# sequencer.net
KiCad netlist of a schematic drawn in EAGLE
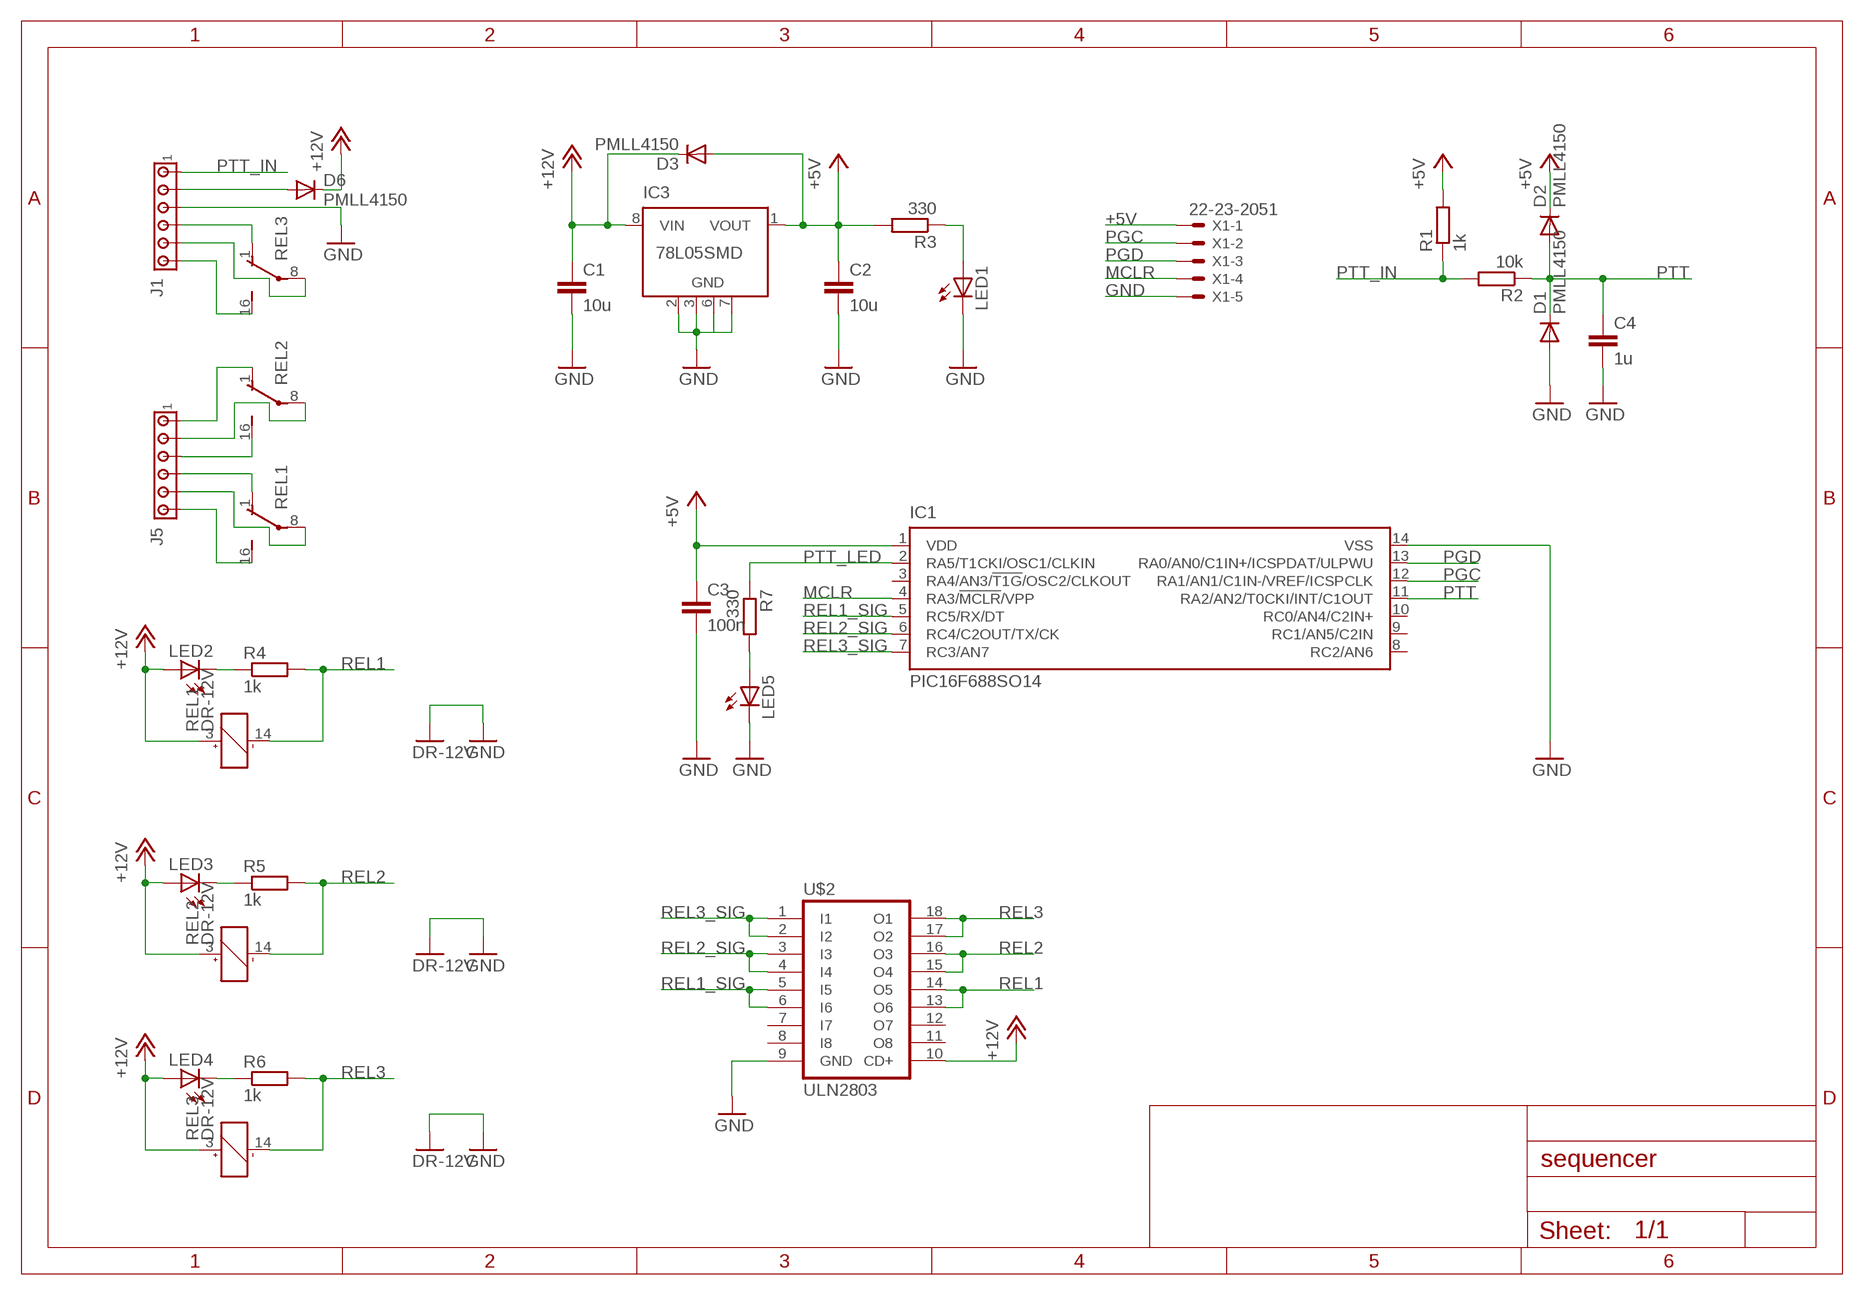
[diagram p0: schematic, sheet 1]

(export (version "E")
  (design (tool "Eeschema 10.0.6"))
  (components
    (comp (ref "C1")
      (value "10u")
      (footprint "eagle-import:C1206")
      (libsource (lib "eagle-import") (part "CAPACITORC1206"))
    )
    (comp (ref "C2")
      (value "10u")
      (footprint "eagle-import:C1206")
      (libsource (lib "eagle-import") (part "CAPACITORC1206"))
    )
    (comp (ref "C3")
      (value "100n")
      (footprint "eagle-import:C1206")
      (libsource (lib "eagle-import") (part "CAPACITORC1206"))
    )
    (comp (ref "C4")
      (value "1u")
      (footprint "eagle-import:C1206")
      (libsource (lib "eagle-import") (part "CAPACITORC1206"))
    )
    (comp (ref "D1")
      (value "PMLL4150")
      (footprint "eagle-import:SOD80C")
      (libsource (lib "eagle-import") (part "PMLL4150"))
    )
    (comp (ref "D2")
      (value "PMLL4150")
      (footprint "eagle-import:SOD80C")
      (libsource (lib "eagle-import") (part "PMLL4150"))
    )
    (comp (ref "D3")
      (value "PMLL4150")
      (footprint "eagle-import:SOD80C")
      (libsource (lib "eagle-import") (part "PMLL4150"))
    )
    (comp (ref "D6")
      (value "PMLL4150")
      (footprint "eagle-import:SOD80C")
      (libsource (lib "eagle-import") (part "PMLL4150"))
    )
    (comp (ref "IC1")
      (value "PIC16F688SO14")
      (footprint "eagle-import:SO14")
      (libsource (lib "eagle-import") (part "PIC16F688SO14"))
    )
    (comp (ref "IC3")
      (value "78L05SMD")
      (footprint "eagle-import:SO08")
      (libsource (lib "eagle-import") (part "78LSMD05"))
    )
    (comp (ref "J1")
      (value "SL508_6_90SL508_6_90")
      (footprint "eagle-import:SL508_6_90")
      (libsource (lib "eagle-import") (part "SL508_6_90SL508_6_90"))
    )
    (comp (ref "J5")
      (value "SL508_6_90SL508_6_90")
      (footprint "eagle-import:SL508_6_90")
      (libsource (lib "eagle-import") (part "SL508_6_90SL508_6_90"))
    )
    (comp (ref "LED1")
      (value "LEDSMT1206")
      (footprint "eagle-import:1206")
      (libsource (lib "eagle-import") (part "LEDSMT1206"))
    )
    (comp (ref "LED2")
      (value "LEDSMT1206")
      (footprint "eagle-import:1206")
      (libsource (lib "eagle-import") (part "LEDSMT1206"))
    )
    (comp (ref "LED3")
      (value "LEDSMT1206")
      (footprint "eagle-import:1206")
      (libsource (lib "eagle-import") (part "LEDSMT1206"))
    )
    (comp (ref "LED4")
      (value "LEDSMT1206")
      (footprint "eagle-import:1206")
      (libsource (lib "eagle-import") (part "LEDSMT1206"))
    )
    (comp (ref "LED5")
      (value "LEDSMT1206")
      (footprint "eagle-import:1206")
      (libsource (lib "eagle-import") (part "LEDSMT1206"))
    )
    (comp (ref "R1")
      (value "1k")
      (footprint "eagle-import:R1206")
      (libsource (lib "eagle-import") (part "RESISTORR1206"))
    )
    (comp (ref "R2")
      (value "10k")
      (footprint "eagle-import:R1206")
      (libsource (lib "eagle-import") (part "RESISTORR1206"))
    )
    (comp (ref "R3")
      (value "330")
      (footprint "eagle-import:R1206")
      (libsource (lib "eagle-import") (part "RESISTORR1206"))
    )
    (comp (ref "R4")
      (value "1k")
      (footprint "eagle-import:R1206")
      (libsource (lib "eagle-import") (part "RESISTORR1206"))
    )
    (comp (ref "R5")
      (value "1k")
      (footprint "eagle-import:R1206")
      (libsource (lib "eagle-import") (part "RESISTORR1206"))
    )
    (comp (ref "R6")
      (value "1k")
      (footprint "eagle-import:R1206")
      (libsource (lib "eagle-import") (part "RESISTORR1206"))
    )
    (comp (ref "R7")
      (value "330")
      (footprint "eagle-import:R1206")
      (libsource (lib "eagle-import") (part "RESISTORR1206"))
    )
    (comp (ref "REL1")
      (value "DR-12V")
      (footprint "eagle-import:DR-12V")
      (libsource (lib "eagle-import") (part "DR-12V"))
    )
    (comp (ref "REL2")
      (value "DR-12V")
      (footprint "eagle-import:DR-12V")
      (libsource (lib "eagle-import") (part "DR-12V"))
    )
    (comp (ref "REL3")
      (value "DR-12V")
      (footprint "eagle-import:DR-12V")
      (libsource (lib "eagle-import") (part "DR-12V"))
    )
    (comp (ref "U$2")
      (value "ULN2803")
      (footprint "eagle-import:SO18W")
      (libsource (lib "eagle-import") (part "ULN2803"))
    )
    (comp (ref "X1")
      (value "22-23-2051")
      (footprint "eagle-import:22-23-2051")
      (fields (field (name "MF") "MOLEX"))
      (libsource (lib "eagle-import") (part "22-23-2051"))
    )
  )
  (nets
    (net (code "1") (name "+5V") (class "Default")
      (node (ref "C2") (pin "1") (pinfunction "1_1") (pintype "passive"))
      (node (ref "C3") (pin "1") (pinfunction "1_1") (pintype "passive"))
      (node (ref "D2") (pin "C") (pinfunction "C_C") (pintype "passive"))
      (node (ref "D3") (pin "A") (pinfunction "A_A") (pintype "passive"))
      (node (ref "IC1") (pin "1") (pinfunction "VDD_1") (pintype "power_in"))
      (node (ref "IC3") (pin "1") (pinfunction "VOUT_1") (pintype "output"))
      (node (ref "R1") (pin "2") (pinfunction "2_2") (pintype "passive"))
      (node (ref "R3") (pin "2") (pinfunction "2_2") (pintype "passive"))
      (node (ref "X1") (pin "1") (pinfunction "S_1") (pintype "passive"))
    )
    (net (code "2") (name "+12V") (class "Default")
      (node (ref "C1") (pin "1") (pinfunction "1_1") (pintype "passive"))
      (node (ref "D3") (pin "C") (pinfunction "C_C") (pintype "passive"))
      (node (ref "D6") (pin "C") (pinfunction "C_C") (pintype "passive"))
      (node (ref "IC3") (pin "8") (pinfunction "VIN_8") (pintype "passive"))
      (node (ref "LED2") (pin "A") (pinfunction "A_A") (pintype "passive"))
      (node (ref "LED3") (pin "A") (pinfunction "A_A") (pintype "passive"))
      (node (ref "LED4") (pin "A") (pinfunction "A_A") (pintype "passive"))
      (node (ref "REL1") (pin "3") (pinfunction "+_3") (pintype "passive"))
      (node (ref "REL2") (pin "3") (pinfunction "+_3") (pintype "passive"))
      (node (ref "REL3") (pin "3") (pinfunction "+_3") (pintype "passive"))
      (node (ref "U$2") (pin "10") (pinfunction "CD+_10") (pintype "passive"))
    )
    (net (code "3") (name "/MCLR") (class "Default")
      (node (ref "IC1") (pin "4") (pinfunction "RA3/~{MCLR}/VPP_4") (pintype "bidirectional"))
      (node (ref "X1") (pin "4") (pinfunction "S_4") (pintype "passive"))
    )
    (net (code "4") (name "/PGC") (class "Default")
      (node (ref "IC1") (pin "12") (pinfunction "RA1/AN1/C1IN-/VREF/ICSPCLK_12") (pintype "bidirectional"))
      (node (ref "X1") (pin "2") (pinfunction "S_2") (pintype "passive"))
    )
    (net (code "5") (name "/PGD") (class "Default")
      (node (ref "IC1") (pin "13") (pinfunction "RA0/AN0/C1IN+/ICSPDAT/ULPWU_13") (pintype "bidirectional"))
      (node (ref "X1") (pin "3") (pinfunction "S_3") (pintype "passive"))
    )
    (net (code "6") (name "/PTT") (class "Default")
      (node (ref "C4") (pin "1") (pinfunction "1_1") (pintype "passive"))
      (node (ref "D1") (pin "C") (pinfunction "C_C") (pintype "passive"))
      (node (ref "D2") (pin "A") (pinfunction "A_A") (pintype "passive"))
      (node (ref "IC1") (pin "11") (pinfunction "RA2/AN2/T0CKI/INT/C1OUT_11") (pintype "bidirectional"))
      (node (ref "R2") (pin "1") (pinfunction "1_1") (pintype "passive"))
    )
    (net (code "7") (name "/PTT_IN") (class "Default")
      (node (ref "J1") (pin "1") (pinfunction "1_1") (pintype "passive"))
      (node (ref "R1") (pin "1") (pinfunction "1_1") (pintype "passive"))
      (node (ref "R2") (pin "2") (pinfunction "2_2") (pintype "passive"))
    )
    (net (code "8") (name "/PTT_LED") (class "Default")
      (node (ref "IC1") (pin "2") (pinfunction "RA5/T1CKI/OSC1/CLKIN_2") (pintype "input"))
      (node (ref "R7") (pin "1") (pinfunction "1_1") (pintype "passive"))
    )
    (net (code "9") (name "/REL1") (class "Default")
      (node (ref "R4") (pin "2") (pinfunction "2_2") (pintype "passive"))
      (node (ref "REL1") (pin "14") (pinfunction "-_14") (pintype "passive"))
      (node (ref "U$2") (pin "13") (pinfunction "O6_13") (pintype "open_collector"))
      (node (ref "U$2") (pin "14") (pinfunction "O5_14") (pintype "open_collector"))
    )
    (net (code "10") (name "/REL1_SIG") (class "Default")
      (node (ref "IC1") (pin "5") (pinfunction "RC5/RX/DT_5") (pintype "bidirectional"))
      (node (ref "U$2") (pin "5") (pinfunction "I5_5") (pintype "input"))
      (node (ref "U$2") (pin "6") (pinfunction "I6_6") (pintype "input"))
    )
    (net (code "11") (name "/REL2") (class "Default")
      (node (ref "R5") (pin "2") (pinfunction "2_2") (pintype "passive"))
      (node (ref "REL2") (pin "14") (pinfunction "-_14") (pintype "passive"))
      (node (ref "U$2") (pin "15") (pinfunction "O4_15") (pintype "open_collector"))
      (node (ref "U$2") (pin "16") (pinfunction "O3_16") (pintype "open_collector"))
    )
    (net (code "12") (name "/REL2_SIG") (class "Default")
      (node (ref "IC1") (pin "6") (pinfunction "RC4/C2OUT/TX/CK_6") (pintype "bidirectional"))
      (node (ref "U$2") (pin "3") (pinfunction "I3_3") (pintype "input"))
      (node (ref "U$2") (pin "4") (pinfunction "I4_4") (pintype "input"))
    )
    (net (code "13") (name "/REL3") (class "Default")
      (node (ref "R6") (pin "2") (pinfunction "2_2") (pintype "passive"))
      (node (ref "REL3") (pin "14") (pinfunction "-_14") (pintype "passive"))
      (node (ref "U$2") (pin "17") (pinfunction "O2_17") (pintype "open_collector"))
      (node (ref "U$2") (pin "18") (pinfunction "O1_18") (pintype "open_collector"))
    )
    (net (code "14") (name "/REL3_SIG") (class "Default")
      (node (ref "IC1") (pin "7") (pinfunction "RC3/AN7_7") (pintype "bidirectional"))
      (node (ref "U$2") (pin "1") (pinfunction "I1_1") (pintype "input"))
      (node (ref "U$2") (pin "2") (pinfunction "I2_2") (pintype "input"))
    )
    (net (code "15") (name "GND") (class "Default")
      (node (ref "C1") (pin "2") (pinfunction "2_2") (pintype "passive"))
      (node (ref "C2") (pin "2") (pinfunction "2_2") (pintype "passive"))
      (node (ref "C3") (pin "2") (pinfunction "2_2") (pintype "passive"))
      (node (ref "C4") (pin "2") (pinfunction "2_2") (pintype "passive"))
      (node (ref "D1") (pin "A") (pinfunction "A_A") (pintype "passive"))
      (node (ref "IC1") (pin "14") (pinfunction "VSS_14") (pintype "power_in"))
      (node (ref "IC3") (pin "2") (pinfunction "GND_2") (pintype "power_in"))
      (node (ref "IC3") (pin "3") (pinfunction "GND_3") (pintype "power_in"))
      (node (ref "IC3") (pin "6") (pinfunction "GND_6") (pintype "power_in"))
      (node (ref "IC3") (pin "7") (pinfunction "GND_7") (pintype "power_in"))
      (node (ref "J1") (pin "3") (pinfunction "3_3") (pintype "passive"))
      (node (ref "LED1") (pin "C") (pinfunction "C_C") (pintype "passive"))
      (node (ref "LED5") (pin "C") (pinfunction "C_C") (pintype "passive"))
      (node (ref "REL1") (pin "9") (pinfunction "GND_9") (pintype "power_in"))
      (node (ref "REL2") (pin "9") (pinfunction "GND_9") (pintype "power_in"))
      (node (ref "REL3") (pin "9") (pinfunction "GND_9") (pintype "power_in"))
      (node (ref "U$2") (pin "9") (pinfunction "GND_9") (pintype "power_in"))
      (node (ref "X1") (pin "5") (pinfunction "S_5") (pintype "passive"))
    )
    (net (code "16") (name "Net-(D6-PadA)") (class "Default")
      (node (ref "D6") (pin "A") (pinfunction "A_A") (pintype "passive"))
      (node (ref "J1") (pin "2") (pinfunction "2_2") (pintype "passive"))
    )
    (net (code "17") (name "Net-(LED1-PadA)") (class "Default")
      (node (ref "LED1") (pin "A") (pinfunction "A_A") (pintype "passive"))
      (node (ref "R3") (pin "1") (pinfunction "1_1") (pintype "passive"))
    )
    (net (code "18") (name "Net-(LED2-PadC)") (class "Default")
      (node (ref "LED2") (pin "C") (pinfunction "C_C") (pintype "passive"))
      (node (ref "R4") (pin "1") (pinfunction "1_1") (pintype "passive"))
    )
    (net (code "19") (name "Net-(LED3-PadC)") (class "Default")
      (node (ref "LED3") (pin "C") (pinfunction "C_C") (pintype "passive"))
      (node (ref "R5") (pin "1") (pinfunction "1_1") (pintype "passive"))
    )
    (net (code "20") (name "Net-(LED4-PadC)") (class "Default")
      (node (ref "LED4") (pin "C") (pinfunction "C_C") (pintype "passive"))
      (node (ref "R6") (pin "1") (pinfunction "1_1") (pintype "passive"))
    )
    (net (code "21") (name "Net-(LED5-PadA)") (class "Default")
      (node (ref "LED5") (pin "A") (pinfunction "A_A") (pintype "passive"))
      (node (ref "R7") (pin "2") (pinfunction "2_2") (pintype "passive"))
    )
    (net (code "22") (name "Net-(REL1B-O)") (class "Default")
      (node (ref "J5") (pin "4") (pinfunction "4_4") (pintype "passive"))
      (node (ref "REL1") (pin "1") (pinfunction "O_1") (pintype "passive"))
    )
    (net (code "23") (name "Net-(REL1B-P)") (class "Default")
      (node (ref "J5") (pin "5") (pinfunction "5_5") (pintype "passive"))
      (node (ref "REL1") (pin "8") (pinfunction "P_8") (pintype "passive"))
    )
    (net (code "24") (name "Net-(REL1B-S)") (class "Default")
      (node (ref "J5") (pin "6") (pinfunction "6_6") (pintype "passive"))
      (node (ref "REL1") (pin "16") (pinfunction "S_16") (pintype "passive"))
    )
    (net (code "25") (name "Net-(REL2B-O)") (class "Default")
      (node (ref "J5") (pin "1") (pinfunction "1_1") (pintype "passive"))
      (node (ref "REL2") (pin "1") (pinfunction "O_1") (pintype "passive"))
    )
    (net (code "26") (name "Net-(REL2B-P)") (class "Default")
      (node (ref "J5") (pin "2") (pinfunction "2_2") (pintype "passive"))
      (node (ref "REL2") (pin "8") (pinfunction "P_8") (pintype "passive"))
    )
    (net (code "27") (name "Net-(REL2B-S)") (class "Default")
      (node (ref "J5") (pin "3") (pinfunction "3_3") (pintype "passive"))
      (node (ref "REL2") (pin "16") (pinfunction "S_16") (pintype "passive"))
    )
    (net (code "28") (name "Net-(REL3B-O)") (class "Default")
      (node (ref "J1") (pin "4") (pinfunction "4_4") (pintype "passive"))
      (node (ref "REL3") (pin "1") (pinfunction "O_1") (pintype "passive"))
    )
    (net (code "29") (name "Net-(REL3B-P)") (class "Default")
      (node (ref "J1") (pin "5") (pinfunction "5_5") (pintype "passive"))
      (node (ref "REL3") (pin "8") (pinfunction "P_8") (pintype "passive"))
    )
    (net (code "30") (name "Net-(REL3B-S)") (class "Default")
      (node (ref "J1") (pin "6") (pinfunction "6_6") (pintype "passive"))
      (node (ref "REL3") (pin "16") (pinfunction "S_16") (pintype "passive"))
    )
    (net (code "31") (name "unconnected-(IC1-RA4{slash}AN3{slash}~{T1G}{slash}OSC2{slash}CLKOUT-Pad3)") (class "Default")
      (node (ref "IC1") (pin "3") (pinfunction "RA4/AN3/~{T1G}/OSC2/CLKOUT_3") (pintype "bidirectional"))
    )
    (net (code "32") (name "unconnected-(IC1-RC0{slash}AN4{slash}C2IN+-Pad10)") (class "Default")
      (node (ref "IC1") (pin "10") (pinfunction "RC0/AN4/C2IN+_10") (pintype "bidirectional"))
    )
    (net (code "33") (name "unconnected-(IC1-RC1{slash}AN5{slash}C2IN-Pad9)") (class "Default")
      (node (ref "IC1") (pin "9") (pinfunction "RC1/AN5/C2IN_9") (pintype "bidirectional"))
    )
    (net (code "34") (name "unconnected-(IC1-RC2{slash}AN6-Pad8)") (class "Default")
      (node (ref "IC1") (pin "8") (pinfunction "RC2/AN6_8") (pintype "bidirectional"))
    )
    (net (code "35") (name "unconnected-(U$2-I7-Pad7)") (class "Default")
      (node (ref "U$2") (pin "7") (pinfunction "I7_7") (pintype "input"))
    )
    (net (code "36") (name "unconnected-(U$2-I8-Pad8)") (class "Default")
      (node (ref "U$2") (pin "8") (pinfunction "I8_8") (pintype "input"))
    )
    (net (code "37") (name "unconnected-(U$2-O7-Pad12)") (class "Default")
      (node (ref "U$2") (pin "12") (pinfunction "O7_12") (pintype "open_collector"))
    )
    (net (code "38") (name "unconnected-(U$2-O8-Pad11)") (class "Default")
      (node (ref "U$2") (pin "11") (pinfunction "O8_11") (pintype "open_collector"))
    )
  )
)
